# BUCK_Module_2596_ADJ.net
KiCad netlist of a schematic drawn in Altium Designer
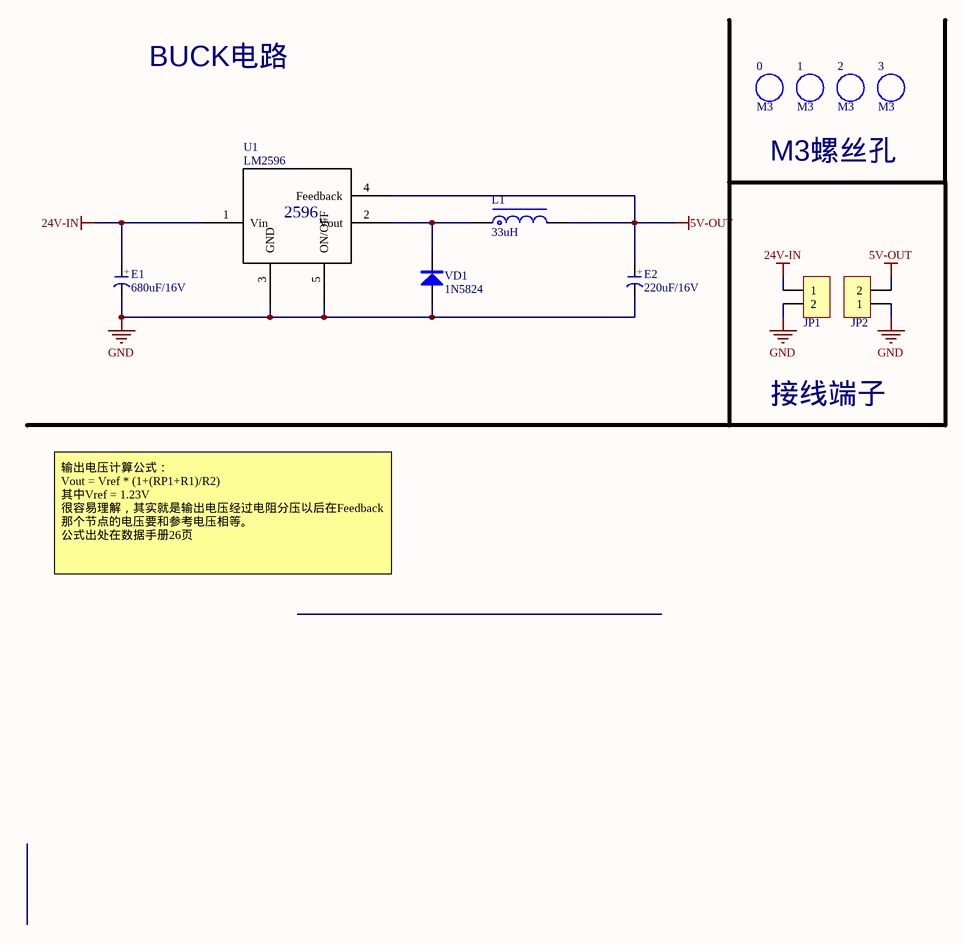
[diagram p0: BUCK_Module_2596_ADJ.SchDoc]

(export (version "E")
  (design (tool "Eeschema 10.0.6"))
  (components
    (comp (ref "0")
      (value "M3")
      (footprint "M3 125X200")
      (description "铜柱孔")
      (fields (field (name "版权归属") "源创客"))
      (libsource (lib "未分类器件") (part "M3"))
    )
    (comp (ref "1")
      (value "M3")
      (footprint "M3 125X200")
      (description "铜柱孔")
      (fields (field (name "版权归属") "源创客"))
      (libsource (lib "未分类器件") (part "M3"))
    )
    (comp (ref "2")
      (value "M3")
      (footprint "M3 125X200")
      (description "铜柱孔")
      (fields (field (name "版权归属") "源创客"))
      (libsource (lib "未分类器件") (part "M3"))
    )
    (comp (ref "3")
      (value "M3")
      (footprint "M3 125X200")
      (description "铜柱孔")
      (fields (field (name "版权归属") "源创客"))
      (libsource (lib "未分类器件") (part "M3"))
    )
    (comp (ref "E1")
      (value "680uF/16V")
      (footprint "CM D(6.3*5.4)")
      (description "贴片电解电容")
      (fields (field (name "版权归属") "源创客"))
      (libsource (lib "电阻-电容-电感") (part "C-CM"))
    )
    (comp (ref "E2")
      (value "220uF/16V")
      (footprint "CM D(6.3*7.7)")
      (description "贴片电解电容")
      (fields (field (name "版权归属") "源创客"))
      (libsource (lib "电阻-电容-电感") (part "C-CM"))
    )
    (comp (ref "JP1")
      (value "HDR-1X2")
      (footprint "KF301-2P")
      (description "2P接插件")
      (fields (field (name "版权归属") "源创客"))
      (libsource (lib "") (part "Header 2_1"))
    )
    (comp (ref "JP2")
      (value "HDR-1X2")
      (footprint "KF301-2P")
      (description "2P接插件")
      (fields (field (name "版权归属") "源创客"))
      (libsource (lib "接插件") (part "Header 2"))
    )
    (comp (ref "L1")
      (value "33uH")
      (footprint "CDRH127")
      (description "功率屏蔽电感")
      (fields (field (name "版权归属") "源创客"))
      (libsource (lib "电阻-电容-电感") (part "L-CDRH"))
    )
    (comp (ref "U1")
      (value "LM2596")
      (footprint "LM2596")
      (libsource (lib "Multicoloredstone's_IC_Lib") (part "LM2596"))
    )
    (comp (ref "VD1")
      (value "1N5824")
      (footprint "SMB")
      (description "肖特基二极管")
      (fields (field (name "版权归属") "源创客"))
      (libsource (lib "二极管-整流桥") (part "SS24"))
    )
  )
  (nets
    (net (code "1") (name "5V-OUT") (class "Default")
      (node (ref "E2") (pin "1") (pinfunction "A_1") (pintype "passive"))
      (node (ref "JP2") (pin "2") (pinfunction "2_2") (pintype "passive"))
      (node (ref "L1") (pin "2") (pinfunction "2_2") (pintype "passive"))
      (node (ref "U1") (pin "4") (pinfunction "Feedback_4") (pintype "passive"))
    )
    (net (code "2") (name "24V-IN") (class "Default")
      (node (ref "E1") (pin "1") (pinfunction "A_1") (pintype "passive"))
      (node (ref "JP1") (pin "1") (pinfunction "1_1") (pintype "passive"))
      (node (ref "U1") (pin "1") (pinfunction "Vin_1") (pintype "passive"))
    )
    (net (code "3") (name "GND") (class "Default")
      (node (ref "E1") (pin "2") (pinfunction "K_2") (pintype "passive"))
      (node (ref "E2") (pin "2") (pinfunction "K_2") (pintype "passive"))
      (node (ref "JP1") (pin "2") (pinfunction "2_2") (pintype "passive"))
      (node (ref "JP2") (pin "1") (pinfunction "1_1") (pintype "passive"))
      (node (ref "U1") (pin "3") (pinfunction "GND_3") (pintype "passive"))
      (node (ref "U1") (pin "5") (pinfunction "ON/OFF_5") (pintype "passive"))
      (node (ref "VD1") (pin "1") (pinfunction "A_1") (pintype "passive"))
    )
    (net (code "4") (name "Net-(U1-Vout)") (class "Default")
      (node (ref "L1") (pin "1") (pinfunction "1_1") (pintype "passive"))
      (node (ref "U1") (pin "2") (pinfunction "Vout_2") (pintype "passive"))
      (node (ref "VD1") (pin "2") (pinfunction "K_2") (pintype "passive"))
    )
  )
)
